# stm32f103.net
KiCad netlist of a schematic drawn in Altium Designer
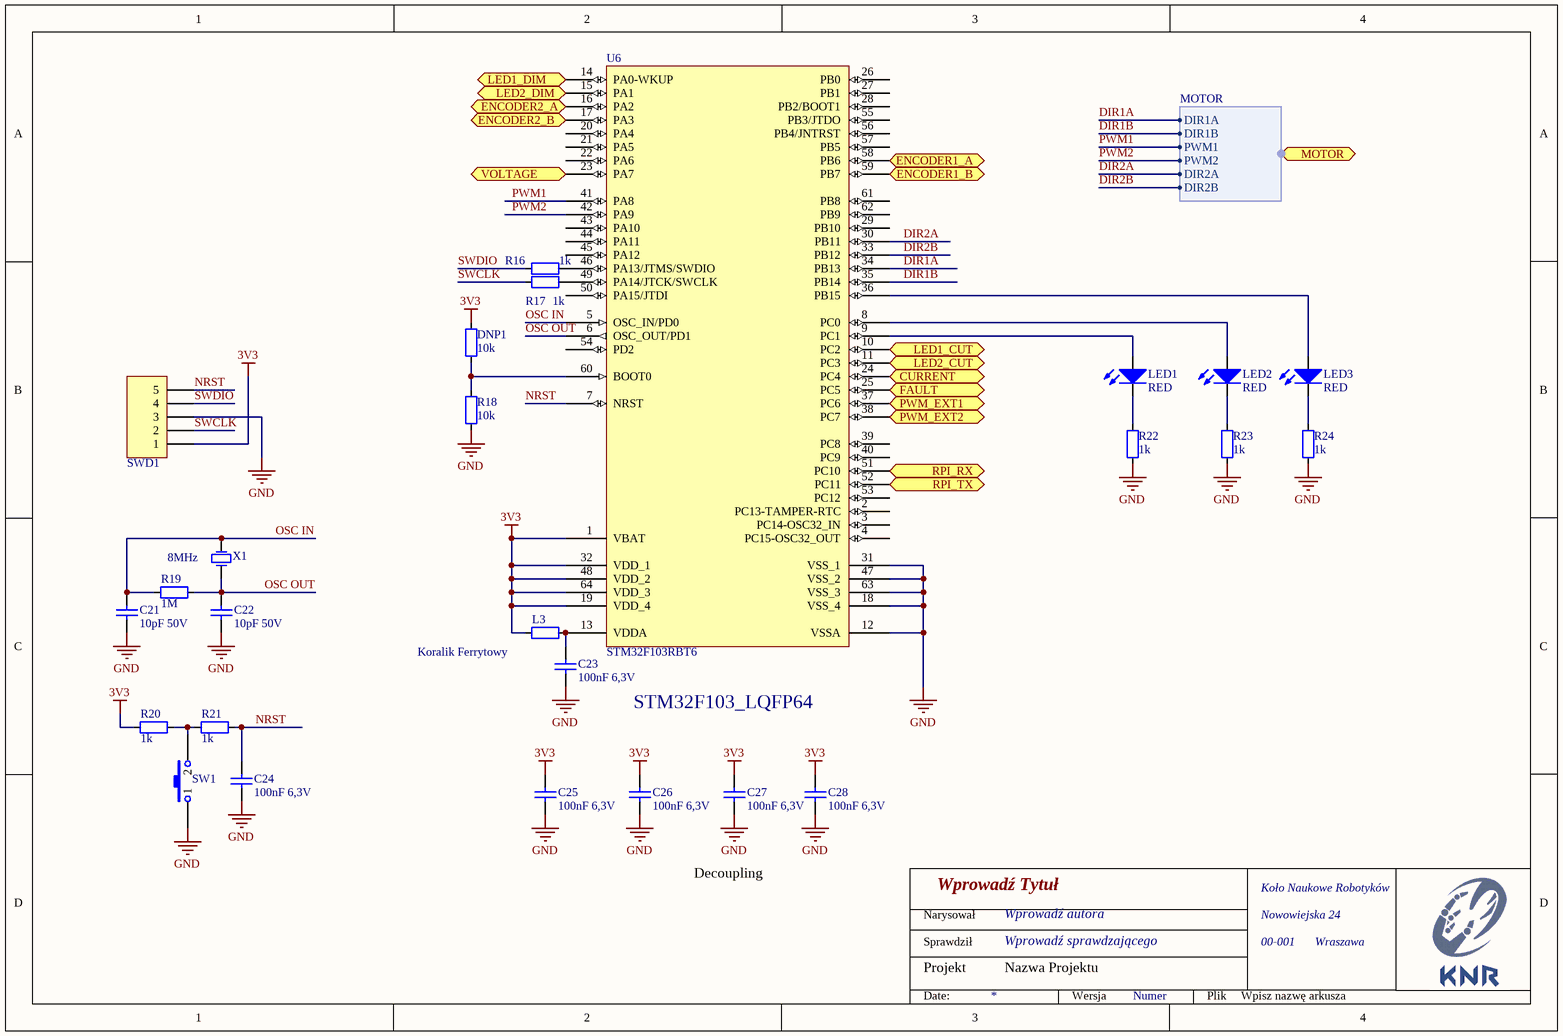
[diagram p0: stm32f103.SchDoc]

(export (version "E")
  (design (tool "Eeschema 10.0.6"))
  (components
    (comp (ref "C21")
      (value "10pF 50V")
      (footprint "0603_CAP")
      (description "Ceramic capacitor")
      (libsource (lib "Library_Altium_KNR") (part "Cap"))
    )
    (comp (ref "C22")
      (value "10pF 50V")
      (footprint "0603_CAP")
      (description "Ceramic capacitor")
      (libsource (lib "Library_Altium_KNR") (part "Cap"))
    )
    (comp (ref "C23")
      (value "100nF 6,3V")
      (footprint "0603_CAP")
      (description "Ceramic capacitor")
      (libsource (lib "Library_Altium_KNR") (part "Cap"))
    )
    (comp (ref "C24")
      (value "100nF 6,3V")
      (footprint "0603_CAP")
      (description "Ceramic capacitor")
      (libsource (lib "Library_Altium_KNR") (part "Cap"))
    )
    (comp (ref "C25")
      (value "100nF 6,3V")
      (footprint "0603_CAP")
      (description "Ceramic capacitor")
      (libsource (lib "Library_Altium_KNR") (part "Cap"))
    )
    (comp (ref "C26")
      (value "100nF 6,3V")
      (footprint "0603_CAP")
      (description "Ceramic capacitor")
      (libsource (lib "Library_Altium_KNR") (part "Cap"))
    )
    (comp (ref "C27")
      (value "100nF 6,3V")
      (footprint "0603_CAP")
      (description "Ceramic capacitor")
      (libsource (lib "Library_Altium_KNR") (part "Cap"))
    )
    (comp (ref "C28")
      (value "100nF 6,3V")
      (footprint "0603_CAP")
      (description "Ceramic capacitor")
      (libsource (lib "Library_Altium_KNR") (part "Cap"))
    )
    (comp (ref "DNP1")
      (value "10k")
      (footprint "0603")
      (description "Resistior")
      (libsource (lib "Library_Altium_KNR") (part "RES"))
    )
    (comp (ref "L3")
      (value "Koralik Ferrytowy")
      (footprint "0603")
      (description "Resistior")
      (libsource (lib "") (part "RES_1"))
    )
    (comp (ref "LED1")
      (value "RED")
      (footprint "0603_led_green")
      (description "Light-emitting diode")
      (libsource (lib "KNR_Kurs") (part "LED"))
    )
    (comp (ref "LED2")
      (value "RED")
      (footprint "0603_led_red")
      (description "Light-emitting diode")
      (libsource (lib "KNR_Kurs") (part "LED"))
    )
    (comp (ref "LED3")
      (value "RED")
      (footprint "0603_led_blue")
      (description "Light-emitting diode")
      (libsource (lib "KNR_Kurs") (part "LED"))
    )
    (comp (ref "R16")
      (value "1k")
      (footprint "0603")
      (description "Resistior")
      (libsource (lib "") (part "RES_1"))
    )
    (comp (ref "R17")
      (value "1k")
      (footprint "0603")
      (description "Resistior")
      (libsource (lib "") (part "RES_1"))
    )
    (comp (ref "R18")
      (value "10k")
      (footprint "0603")
      (description "Resistior")
      (libsource (lib "Library_Altium_KNR") (part "RES"))
    )
    (comp (ref "R19")
      (value "1M")
      (footprint "0603")
      (description "Resistior")
      (libsource (lib "") (part "RES_2"))
    )
    (comp (ref "R20")
      (value "1k")
      (footprint "0603")
      (description "Resistior")
      (libsource (lib "Library_Altium_KNR") (part "RES"))
    )
    (comp (ref "R21")
      (value "1k")
      (footprint "0603")
      (description "Resistior")
      (libsource (lib "Library_Altium_KNR") (part "RES"))
    )
    (comp (ref "R22")
      (value "1k")
      (footprint "RES_0603")
      (description "Default resistor")
      (libsource (lib "Resistors") (part "Resistor"))
    )
    (comp (ref "R23")
      (value "1k")
      (footprint "RES_0603")
      (description "Default resistor")
      (libsource (lib "Resistors") (part "Resistor"))
    )
    (comp (ref "R24")
      (value "1k")
      (footprint "RES_0603")
      (description "Default resistor")
      (libsource (lib "Resistors") (part "Resistor"))
    )
    (comp (ref "SW1")
      (value "Micro_Switch")
      (footprint "Tact 34N-F")
      (description "Switch")
      (fields (field (name "PUBLISHER") "Altium Limited"))
      (libsource (lib "KNR_Kurs") (part "Micro_Switch"))
    )
    (comp (ref "SWD1")
      (value "HDR1X5")
      (footprint "Molex SPOX Horizontal 5 Circuits")
      (description "Header, 5-Pin")
      (fields (field (name "PUBLISHER") "Altium Limited"))
      (libsource (lib "Library_Altium_KNR") (part "HDR1X5"))
    )
    (comp (ref "U6")
      (value "STM32F103RBT6")
      (footprint "LQFP64_L")
      (description "STM32 ARM-based 32-bit")
      (fields (field (name "PUBLISHER") "Altium Limited"))
      (libsource (lib "Library_Altium_KNR") (part "STM32F103RBT6"))
    )
    (comp (ref "X1")
      (value "8MHz")
      (footprint "HC49-4H_THT")
      (description "Oscillator")
      (libsource (lib "KNR_Kurs") (part "XTAL"))
    )
  )
  (nets
    (net (code "2") (name "/CURRENT") (class "Default")
      (node (ref "U6") (pin "24") (pinfunction "PC4_24") (pintype "bidirectional"))
    )
    (net (code "3") (name "/DIR1A") (class "Default")
      (node (ref "U6") (pin "34") (pinfunction "PB13_34") (pintype "bidirectional"))
    )
    (net (code "4") (name "/DIR1B") (class "Default")
      (node (ref "U6") (pin "35") (pinfunction "PB14_35") (pintype "bidirectional"))
    )
    (net (code "5") (name "/DIR2A") (class "Default")
      (node (ref "U6") (pin "30") (pinfunction "PB11_30") (pintype "bidirectional"))
    )
    (net (code "6") (name "/DIR2B") (class "Default")
      (node (ref "U6") (pin "33") (pinfunction "PB12_33") (pintype "bidirectional"))
    )
    (net (code "7") (name "/ENCODER1_A") (class "Default")
      (node (ref "U6") (pin "58") (pinfunction "PB6_58") (pintype "bidirectional"))
    )
    (net (code "8") (name "/ENCODER1_B") (class "Default")
      (node (ref "U6") (pin "59") (pinfunction "PB7_59") (pintype "bidirectional"))
    )
    (net (code "9") (name "/ENCODER2_A") (class "Default")
      (node (ref "U6") (pin "16") (pinfunction "PA2_16") (pintype "bidirectional"))
    )
    (net (code "10") (name "/ENCODER2_B") (class "Default")
      (node (ref "U6") (pin "17") (pinfunction "PA3_17") (pintype "bidirectional"))
    )
    (net (code "11") (name "/FAULT") (class "Default")
      (node (ref "U6") (pin "25") (pinfunction "PC5_25") (pintype "bidirectional"))
    )
    (net (code "12") (name "/LED1_CUT") (class "Default")
      (node (ref "U6") (pin "10") (pinfunction "PC2_10") (pintype "bidirectional"))
    )
    (net (code "13") (name "/LED1_DIM") (class "Default")
      (node (ref "U6") (pin "14") (pinfunction "PA0-WKUP_14") (pintype "bidirectional"))
    )
    (net (code "14") (name "/LED2_CUT") (class "Default")
      (node (ref "U6") (pin "11") (pinfunction "PC3_11") (pintype "bidirectional"))
    )
    (net (code "15") (name "/LED2_DIM") (class "Default")
      (node (ref "U6") (pin "15") (pinfunction "PA1_15") (pintype "bidirectional"))
    )
    (net (code "16") (name "/NRST") (class "Default")
      (node (ref "C24") (pin "1") (pinfunction "1_1") (pintype "passive"))
      (node (ref "R21") (pin "1") (pinfunction "1_1") (pintype "passive"))
      (node (ref "SWD1") (pin "5") (pinfunction "5_5") (pintype "passive"))
      (node (ref "U6") (pin "7") (pinfunction "NRST_7") (pintype "bidirectional"))
    )
    (net (code "17") (name "/OSC IN") (class "Default")
      (node (ref "C21") (pin "1") (pinfunction "1_1") (pintype "passive"))
      (node (ref "R19") (pin "2") (pinfunction "2_2") (pintype "passive"))
      (node (ref "U6") (pin "5") (pinfunction "OSC_IN/PD0_5") (pintype "input"))
      (node (ref "X1") (pin "1") (pinfunction "OSC1_1") (pintype "passive"))
    )
    (net (code "18") (name "/OSC OUT") (class "Default")
      (node (ref "C22") (pin "1") (pinfunction "1_1") (pintype "passive"))
      (node (ref "R19") (pin "1") (pinfunction "1_1") (pintype "passive"))
      (node (ref "U6") (pin "6") (pinfunction "OSC_OUT/PD1_6") (pintype "output"))
      (node (ref "X1") (pin "2") (pinfunction "OSC2_2") (pintype "passive"))
    )
    (net (code "19") (name "/PWM1") (class "Default")
      (node (ref "U6") (pin "41") (pinfunction "PA8_41") (pintype "bidirectional"))
    )
    (net (code "20") (name "/PWM2") (class "Default")
      (node (ref "U6") (pin "42") (pinfunction "PA9_42") (pintype "bidirectional"))
    )
    (net (code "21") (name "/PWM_EXT1") (class "Default")
      (node (ref "U6") (pin "37") (pinfunction "PC6_37") (pintype "bidirectional"))
    )
    (net (code "22") (name "/PWM_EXT2") (class "Default")
      (node (ref "U6") (pin "38") (pinfunction "PC7_38") (pintype "bidirectional"))
    )
    (net (code "23") (name "/RPI_RX") (class "Default")
      (node (ref "U6") (pin "51") (pinfunction "PC10_51") (pintype "bidirectional"))
    )
    (net (code "24") (name "/RPI_TX") (class "Default")
      (node (ref "U6") (pin "52") (pinfunction "PC11_52") (pintype "bidirectional"))
    )
    (net (code "25") (name "/SWCLK") (class "Default")
      (node (ref "R17") (pin "1") (pinfunction "1_1") (pintype "passive"))
      (node (ref "SWD1") (pin "2") (pinfunction "2_2") (pintype "passive"))
    )
    (net (code "26") (name "/SWDIO") (class "Default")
      (node (ref "R16") (pin "1") (pinfunction "1_1") (pintype "passive"))
      (node (ref "SWD1") (pin "4") (pinfunction "4_4") (pintype "passive"))
    )
    (net (code "27") (name "/VOLTAGE") (class "Default")
      (node (ref "U6") (pin "23") (pinfunction "PA7_23") (pintype "bidirectional"))
    )
    (net (code "29") (name "3V3") (class "Default")
      (node (ref "C25") (pin "1") (pinfunction "1_1") (pintype "passive"))
      (node (ref "C26") (pin "1") (pinfunction "1_1") (pintype "passive"))
      (node (ref "C27") (pin "1") (pinfunction "1_1") (pintype "passive"))
      (node (ref "C28") (pin "1") (pinfunction "1_1") (pintype "passive"))
      (node (ref "DNP1") (pin "1") (pinfunction "1_1") (pintype "passive"))
      (node (ref "L3") (pin "1") (pinfunction "1_1") (pintype "passive"))
      (node (ref "R20") (pin "2") (pinfunction "2_2") (pintype "passive"))
      (node (ref "SWD1") (pin "1") (pinfunction "1_1") (pintype "passive"))
      (node (ref "U6") (pin "1") (pinfunction "VBAT_1") (pintype "power_in"))
      (node (ref "U6") (pin "19") (pinfunction "VDD_4_19") (pintype "power_in"))
      (node (ref "U6") (pin "32") (pinfunction "VDD_1_32") (pintype "power_in"))
      (node (ref "U6") (pin "48") (pinfunction "VDD_2_48") (pintype "power_in"))
      (node (ref "U6") (pin "64") (pinfunction "VDD_3_64") (pintype "power_in"))
    )
    (net (code "30") (name "GND") (class "Default")
      (node (ref "C21") (pin "2") (pinfunction "2_2") (pintype "passive"))
      (node (ref "C22") (pin "2") (pinfunction "2_2") (pintype "passive"))
      (node (ref "C23") (pin "2") (pinfunction "2_2") (pintype "passive"))
      (node (ref "C24") (pin "2") (pinfunction "2_2") (pintype "passive"))
      (node (ref "C25") (pin "2") (pinfunction "2_2") (pintype "passive"))
      (node (ref "C26") (pin "2") (pinfunction "2_2") (pintype "passive"))
      (node (ref "C27") (pin "2") (pinfunction "2_2") (pintype "passive"))
      (node (ref "C28") (pin "2") (pinfunction "2_2") (pintype "passive"))
      (node (ref "R18") (pin "2") (pinfunction "2_2") (pintype "passive"))
      (node (ref "R22") (pin "1") (pinfunction "1_1") (pintype "passive"))
      (node (ref "R23") (pin "1") (pinfunction "1_1") (pintype "passive"))
      (node (ref "R24") (pin "1") (pinfunction "1_1") (pintype "passive"))
      (node (ref "SW1") (pin "1") (pinfunction "1_1") (pintype "passive"))
      (node (ref "SWD1") (pin "3") (pinfunction "3_3") (pintype "passive"))
      (node (ref "U6") (pin "12") (pinfunction "VSSA_12") (pintype "power_in"))
      (node (ref "U6") (pin "18") (pinfunction "VSS_4_18") (pintype "power_in"))
      (node (ref "U6") (pin "31") (pinfunction "VSS_1_31") (pintype "power_in"))
      (node (ref "U6") (pin "47") (pinfunction "VSS_2_47") (pintype "power_in"))
      (node (ref "U6") (pin "63") (pinfunction "VSS_3_63") (pintype "power_in"))
    )
    (net (code "31") (name "Net-(LED1-A)") (class "Default")
      (node (ref "LED1") (pin "1") (pinfunction "A_1") (pintype "passive"))
      (node (ref "U6") (pin "9") (pinfunction "PC1_9") (pintype "bidirectional"))
    )
    (net (code "32") (name "Net-(LED1-K)") (class "Default")
      (node (ref "LED1") (pin "2") (pinfunction "K_2") (pintype "passive"))
      (node (ref "R22") (pin "2") (pinfunction "2_2") (pintype "passive"))
    )
    (net (code "33") (name "Net-(LED2-A)") (class "Default")
      (node (ref "LED2") (pin "1") (pinfunction "A_1") (pintype "passive"))
      (node (ref "U6") (pin "8") (pinfunction "PC0_8") (pintype "bidirectional"))
    )
    (net (code "34") (name "Net-(LED2-K)") (class "Default")
      (node (ref "LED2") (pin "2") (pinfunction "K_2") (pintype "passive"))
      (node (ref "R23") (pin "2") (pinfunction "2_2") (pintype "passive"))
    )
    (net (code "35") (name "Net-(LED3-A)") (class "Default")
      (node (ref "LED3") (pin "1") (pinfunction "A_1") (pintype "passive"))
      (node (ref "U6") (pin "36") (pinfunction "PB15_36") (pintype "bidirectional"))
    )
    (net (code "36") (name "Net-(LED3-K)") (class "Default")
      (node (ref "LED3") (pin "2") (pinfunction "K_2") (pintype "passive"))
      (node (ref "R24") (pin "2") (pinfunction "2_2") (pintype "passive"))
    )
    (net (code "37") (name "Net-(R20-Pad1)") (class "Default")
      (node (ref "R20") (pin "1") (pinfunction "1_1") (pintype "passive"))
      (node (ref "R21") (pin "2") (pinfunction "2_2") (pintype "passive"))
      (node (ref "SW1") (pin "2") (pinfunction "2_2") (pintype "passive"))
    )
    (net (code "38") (name "Net-(U6-BOOT0)") (class "Default")
      (node (ref "DNP1") (pin "2") (pinfunction "2_2") (pintype "passive"))
      (node (ref "R18") (pin "1") (pinfunction "1_1") (pintype "passive"))
      (node (ref "U6") (pin "60") (pinfunction "BOOT0_60") (pintype "input"))
    )
    (net (code "39") (name "Net-(U6-PA13{slash}JTMS{slash}SWDIO)") (class "Default")
      (node (ref "R16") (pin "2") (pinfunction "2_2") (pintype "passive"))
      (node (ref "U6") (pin "46") (pinfunction "PA13/JTMS/SWDIO_46") (pintype "bidirectional"))
    )
    (net (code "40") (name "Net-(U6-PA14{slash}JTCK{slash}SWCLK)") (class "Default")
      (node (ref "R17") (pin "2") (pinfunction "2_2") (pintype "passive"))
      (node (ref "U6") (pin "49") (pinfunction "PA14/JTCK/SWCLK_49") (pintype "bidirectional"))
    )
    (net (code "41") (name "Net-(U6-VDDA)") (class "Default")
      (node (ref "C23") (pin "1") (pinfunction "1_1") (pintype "passive"))
      (node (ref "L3") (pin "2") (pinfunction "2_2") (pintype "passive"))
      (node (ref "U6") (pin "13") (pinfunction "VDDA_13") (pintype "power_in"))
    )
    (net (code "42") (name "unconnected-(U6-PA4-Pad20)") (class "Default")
      (node (ref "U6") (pin "20") (pinfunction "PA4_20") (pintype "bidirectional"))
    )
    (net (code "43") (name "unconnected-(U6-PA5-Pad21)") (class "Default")
      (node (ref "U6") (pin "21") (pinfunction "PA5_21") (pintype "bidirectional"))
    )
    (net (code "44") (name "unconnected-(U6-PA6-Pad22)") (class "Default")
      (node (ref "U6") (pin "22") (pinfunction "PA6_22") (pintype "bidirectional"))
    )
    (net (code "45") (name "unconnected-(U6-PA10-Pad43)") (class "Default")
      (node (ref "U6") (pin "43") (pinfunction "PA10_43") (pintype "bidirectional"))
    )
    (net (code "46") (name "unconnected-(U6-PA11-Pad44)") (class "Default")
      (node (ref "U6") (pin "44") (pinfunction "PA11_44") (pintype "bidirectional"))
    )
    (net (code "47") (name "unconnected-(U6-PA12-Pad45)") (class "Default")
      (node (ref "U6") (pin "45") (pinfunction "PA12_45") (pintype "bidirectional"))
    )
    (net (code "48") (name "unconnected-(U6-PA15{slash}JTDI-Pad50)") (class "Default")
      (node (ref "U6") (pin "50") (pinfunction "PA15/JTDI_50") (pintype "bidirectional"))
    )
    (net (code "49") (name "unconnected-(U6-PB0-Pad26)") (class "Default")
      (node (ref "U6") (pin "26") (pinfunction "PB0_26") (pintype "bidirectional"))
    )
    (net (code "50") (name "unconnected-(U6-PB1-Pad27)") (class "Default")
      (node (ref "U6") (pin "27") (pinfunction "PB1_27") (pintype "bidirectional"))
    )
    (net (code "51") (name "unconnected-(U6-PB2{slash}BOOT1-Pad28)") (class "Default")
      (node (ref "U6") (pin "28") (pinfunction "PB2/BOOT1_28") (pintype "bidirectional"))
    )
    (net (code "52") (name "unconnected-(U6-PB3{slash}JTDO-Pad55)") (class "Default")
      (node (ref "U6") (pin "55") (pinfunction "PB3/JTDO_55") (pintype "bidirectional"))
    )
    (net (code "53") (name "unconnected-(U6-PB4{slash}JNTRST-Pad56)") (class "Default")
      (node (ref "U6") (pin "56") (pinfunction "PB4/JNTRST_56") (pintype "bidirectional"))
    )
    (net (code "54") (name "unconnected-(U6-PB5-Pad57)") (class "Default")
      (node (ref "U6") (pin "57") (pinfunction "PB5_57") (pintype "bidirectional"))
    )
    (net (code "55") (name "unconnected-(U6-PB8-Pad61)") (class "Default")
      (node (ref "U6") (pin "61") (pinfunction "PB8_61") (pintype "bidirectional"))
    )
    (net (code "56") (name "unconnected-(U6-PB9-Pad62)") (class "Default")
      (node (ref "U6") (pin "62") (pinfunction "PB9_62") (pintype "bidirectional"))
    )
    (net (code "57") (name "unconnected-(U6-PB10-Pad29)") (class "Default")
      (node (ref "U6") (pin "29") (pinfunction "PB10_29") (pintype "bidirectional"))
    )
    (net (code "58") (name "unconnected-(U6-PC8-Pad39)") (class "Default")
      (node (ref "U6") (pin "39") (pinfunction "PC8_39") (pintype "bidirectional"))
    )
    (net (code "59") (name "unconnected-(U6-PC9-Pad40)") (class "Default")
      (node (ref "U6") (pin "40") (pinfunction "PC9_40") (pintype "bidirectional"))
    )
    (net (code "60") (name "unconnected-(U6-PC12-Pad53)") (class "Default")
      (node (ref "U6") (pin "53") (pinfunction "PC12_53") (pintype "bidirectional"))
    )
    (net (code "61") (name "unconnected-(U6-PC13-TAMPER-RTC-Pad2)") (class "Default")
      (node (ref "U6") (pin "2") (pinfunction "PC13-TAMPER-RTC_2") (pintype "bidirectional"))
    )
    (net (code "62") (name "unconnected-(U6-PC14-OSC32_IN-Pad3)") (class "Default")
      (node (ref "U6") (pin "3") (pinfunction "PC14-OSC32_IN_3") (pintype "bidirectional"))
    )
    (net (code "63") (name "unconnected-(U6-PC15-OSC32_OUT-Pad4)") (class "Default")
      (node (ref "U6") (pin "4") (pinfunction "PC15-OSC32_OUT_4") (pintype "bidirectional"))
    )
    (net (code "64") (name "unconnected-(U6-PD2-Pad54)") (class "Default")
      (node (ref "U6") (pin "54") (pinfunction "PD2_54") (pintype "bidirectional"))
    )
  )
)
